# M_D_ext_power-with_d.net
KiCad netlist of a schematic drawn in EAGLE
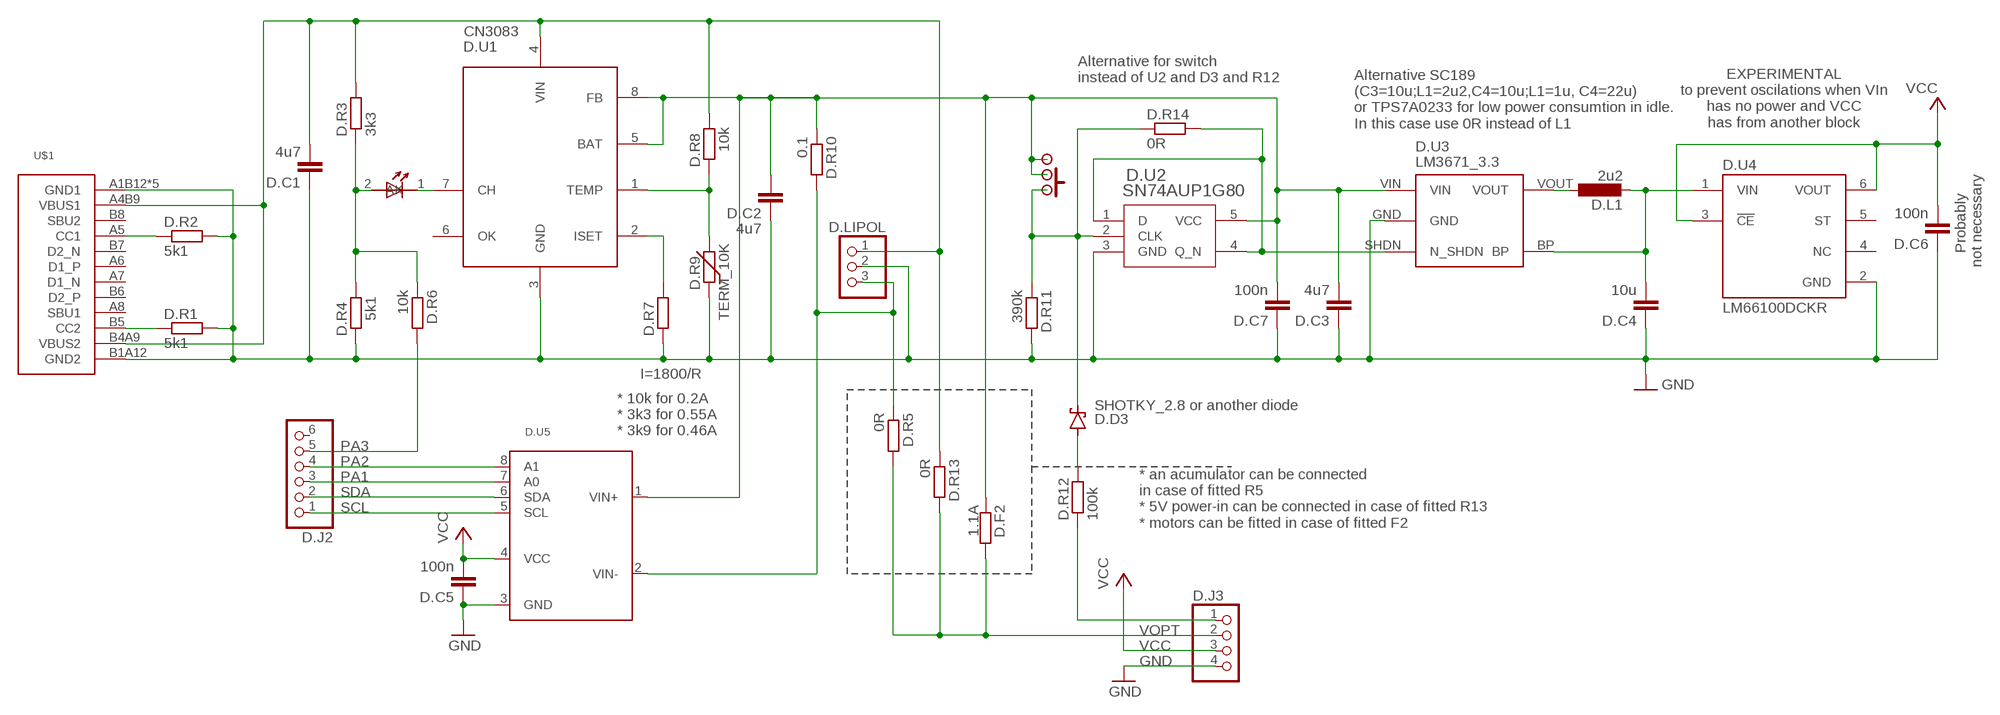
[diagram p0: schematic, sheet 1]

(export (version "E")
  (design (tool "Eeschema 10.0.6"))
  (components
    (comp (ref "D.C1")
      (value "4u7")
      (footprint "eagle-import:C0603")
      (libsource (lib "eagle-import") (part "C-EUC0603"))
    )
    (comp (ref "D.C2")
      (value "4u7")
      (footprint "eagle-import:C0603")
      (libsource (lib "eagle-import") (part "C-EUC0603"))
    )
    (comp (ref "D.C3")
      (value "4u7")
      (footprint "eagle-import:C0603")
      (libsource (lib "eagle-import") (part "C-EUC0603"))
    )
    (comp (ref "D.C4")
      (value "10u")
      (footprint "eagle-import:C0603")
      (libsource (lib "eagle-import") (part "C-EUC0603"))
    )
    (comp (ref "D.C5")
      (value "100n")
      (footprint "eagle-import:C0603")
      (libsource (lib "eagle-import") (part "C-EUC0603"))
    )
    (comp (ref "D.C6")
      (value "100n")
      (footprint "eagle-import:C0603")
      (libsource (lib "eagle-import") (part "C-EUC0603"))
    )
    (comp (ref "D.C7")
      (value "100n")
      (footprint "eagle-import:C0603")
      (libsource (lib "eagle-import") (part "C-EUC0603"))
    )
    (comp (ref "D.D1")
      (value "LED_1.8")
      (footprint "eagle-import:LED_1.8")
      (libsource (lib "eagle-import") (part "LED_1.8"))
    )
    (comp (ref "D.D3")
      (value "SHOTKY_2.8 or another diode")
      (footprint "eagle-import:SHOTKY_2.8")
      (libsource (lib "eagle-import") (part "SHOTKY_2.8"))
    )
    (comp (ref "D.F2")
      (value "1.1A")
      (footprint "eagle-import:R0805")
      (libsource (lib "eagle-import") (part "R-EU_R0805"))
    )
    (comp (ref "D.J2")
      (value "PINHD-1X6")
      (footprint "eagle-import:1X06")
      (libsource (lib "eagle-import") (part "PINHD-1X6"))
    )
    (comp (ref "D.J3")
      (value "PINHD-1X4")
      (footprint "eagle-import:1X04")
      (libsource (lib "eagle-import") (part "PINHD-1X4"))
    )
    (comp (ref "D.L1")
      (value "2u2")
      (footprint "eagle-import:L3230M")
      (libsource (lib "eagle-import") (part "L-EUL3230M"))
    )
    (comp (ref "D.LIPOL")
      (value "PINHEAD-1X3-2")
      (footprint "eagle-import:1X-03-2")
      (libsource (lib "eagle-import") (part "PINHEAD-1X3-2"))
    )
    (comp (ref "D.ON/OFF/RESET")
      (value "SWITCH")
      (footprint "eagle-import:SWITCH")
      (libsource (lib "eagle-import") (part "SWITCH"))
    )
    (comp (ref "D.R1")
      (value "5k1")
      (footprint "eagle-import:R0603")
      (libsource (lib "eagle-import") (part "R-EU_R0603"))
    )
    (comp (ref "D.R2")
      (value "5k1")
      (footprint "eagle-import:R0603")
      (libsource (lib "eagle-import") (part "R-EU_R0603"))
    )
    (comp (ref "D.R3")
      (value "3k3")
      (footprint "eagle-import:R0603")
      (libsource (lib "eagle-import") (part "R-EU_R0603"))
    )
    (comp (ref "D.R4")
      (value "5k1")
      (footprint "eagle-import:R0603")
      (libsource (lib "eagle-import") (part "R-EU_R0603"))
    )
    (comp (ref "D.R5")
      (value "0R")
      (footprint "eagle-import:R0603")
      (libsource (lib "eagle-import") (part "R-EU_R0603"))
    )
    (comp (ref "D.R6")
      (value "10k")
      (footprint "eagle-import:R0603")
      (libsource (lib "eagle-import") (part "R-EU_R0603"))
    )
    (comp (ref "D.R7")
      (value "I=1800/R")
      (footprint "eagle-import:R0603")
      (libsource (lib "eagle-import") (part "R-EU_R0603"))
    )
    (comp (ref "D.R8")
      (value "10k")
      (footprint "eagle-import:R0603")
      (libsource (lib "eagle-import") (part "R-EU_R0603"))
    )
    (comp (ref "D.R9")
      (value "TERM_10K")
      (footprint "eagle-import:THERM")
      (libsource (lib "eagle-import") (part "THERM"))
    )
    (comp (ref "D.R10")
      (value "0.1")
      (footprint "eagle-import:R0805")
      (libsource (lib "eagle-import") (part "R-EU_R0805"))
    )
    (comp (ref "D.R11")
      (value "390k")
      (footprint "eagle-import:R0603")
      (libsource (lib "eagle-import") (part "R-EU_R0603"))
    )
    (comp (ref "D.R12")
      (value "100k")
      (footprint "eagle-import:R0603")
      (libsource (lib "eagle-import") (part "R-EU_R0603"))
    )
    (comp (ref "D.R13")
      (value "0R")
      (footprint "eagle-import:R0603")
      (libsource (lib "eagle-import") (part "R-EU_R0603"))
    )
    (comp (ref "D.R14")
      (value "0R")
      (footprint "eagle-import:R0603")
      (libsource (lib "eagle-import") (part "R-EU_R0603"))
    )
    (comp (ref "D.U1")
      (value "CN3083")
      (footprint "eagle-import:SOP8")
      (libsource (lib "eagle-import") (part "CN3083"))
    )
    (comp (ref "D.U2")
      (value "SN74AUP1G80")
      (footprint "eagle-import:DCK0005A_M")
      (fields
        (field (name "MANUFACTURER_PART_NUMBER") "SN74AUP1G80DCKR")
        (field (name "COPYRIGHT") "Copyright (C) 2026 Ultra Librarian. All rights reserved.")
      )
      (libsource (lib "eagle-import") (part "SN74AUP1G80DCKRDCK0005A_M"))
    )
    (comp (ref "D.U3")
      (value "LM3671_3.3")
      (footprint "eagle-import:SOT32-5")
      (libsource (lib "eagle-import") (part "STABILISER_APE8865"))
    )
    (comp (ref "D.U4")
      (value "LM66100DCKR")
      (footprint "eagle-import:SOT65P210X110-6N")
      (fields (field (name "MF") "Texas Instruments"))
      (libsource (lib "eagle-import") (part "LM66100DCKR"))
    )
    (comp (ref "D.U5")
      (value "INA219")
      (footprint "eagle-import:SOT23-8")
      (libsource (lib "eagle-import") (part "INA219"))
    )
    (comp (ref "U$1")
      (value "USB-C")
      (footprint "eagle-import:USB-C")
      (libsource (lib "eagle-import") (part "USB-C"))
    )
  )
  (nets
    (net (code "1") (name "/PA1") (class "Default")
      (node (ref "D.J2") (pin "3") (pinfunction "3_3") (pintype "passive"))
      (node (ref "D.U5") (pin "7") (pinfunction "A0_7") (pintype "bidirectional"))
    )
    (net (code "2") (name "/PA2") (class "Default")
      (node (ref "D.J2") (pin "4") (pinfunction "4_4") (pintype "passive"))
      (node (ref "D.U5") (pin "8") (pinfunction "A1_8") (pintype "bidirectional"))
    )
    (net (code "3") (name "/PA3") (class "Default")
      (node (ref "D.J2") (pin "5") (pinfunction "5_5") (pintype "passive"))
      (node (ref "D.R6") (pin "2") (pinfunction "2_2") (pintype "passive"))
    )
    (net (code "4") (name "/SCL") (class "Default")
      (node (ref "D.J2") (pin "1") (pinfunction "1_1") (pintype "passive"))
      (node (ref "D.U5") (pin "5") (pinfunction "SCL_5") (pintype "bidirectional"))
    )
    (net (code "5") (name "/SDA") (class "Default")
      (node (ref "D.J2") (pin "2") (pinfunction "2_2") (pintype "passive"))
      (node (ref "D.U5") (pin "6") (pinfunction "SDA_6") (pintype "bidirectional"))
    )
    (net (code "6") (name "/VOPT") (class "Default")
      (node (ref "D.F2") (pin "2") (pinfunction "2_2") (pintype "passive"))
      (node (ref "D.J3") (pin "2") (pinfunction "2_2") (pintype "passive"))
      (node (ref "D.R13") (pin "2") (pinfunction "2_2") (pintype "passive"))
      (node (ref "D.R5") (pin "2") (pinfunction "2_2") (pintype "passive"))
    )
    (net (code "7") (name "GND") (class "Default")
      (node (ref "D.C1") (pin "1") (pinfunction "1_1") (pintype "passive"))
      (node (ref "D.C2") (pin "1") (pinfunction "1_1") (pintype "passive"))
      (node (ref "D.C3") (pin "1") (pinfunction "1_1") (pintype "passive"))
      (node (ref "D.C4") (pin "1") (pinfunction "1_1") (pintype "passive"))
      (node (ref "D.C5") (pin "1") (pinfunction "1_1") (pintype "passive"))
      (node (ref "D.C6") (pin "1") (pinfunction "1_1") (pintype "passive"))
      (node (ref "D.C7") (pin "1") (pinfunction "1_1") (pintype "passive"))
      (node (ref "D.J3") (pin "4") (pinfunction "4_4") (pintype "passive"))
      (node (ref "D.LIPOL") (pin "2") (pinfunction "2_2") (pintype "passive"))
      (node (ref "D.R1") (pin "2") (pinfunction "2_2") (pintype "passive"))
      (node (ref "D.R11") (pin "2") (pinfunction "2_2") (pintype "passive"))
      (node (ref "D.R2") (pin "2") (pinfunction "2_2") (pintype "passive"))
      (node (ref "D.R4") (pin "1") (pinfunction "1_1") (pintype "passive"))
      (node (ref "D.R7") (pin "1") (pinfunction "1_1") (pintype "passive"))
      (node (ref "D.R9") (pin "1") (pinfunction "1_1") (pintype "passive"))
      (node (ref "D.U1") (pin "3") (pinfunction "GND_3") (pintype "bidirectional"))
      (node (ref "D.U2") (pin "3") (pinfunction "GND_3") (pintype "power_in"))
      (node (ref "D.U3") (pin "GND") (pinfunction "GND_GND") (pintype "bidirectional"))
      (node (ref "D.U4") (pin "2") (pinfunction "GND_2") (pintype "power_in"))
      (node (ref "D.U5") (pin "3") (pinfunction "GND_3") (pintype "bidirectional"))
      (node (ref "U$1") (pin "A1B12") (pinfunction "GND1_A1B12") (pintype "bidirectional"))
      (node (ref "U$1") (pin "B1A12") (pinfunction "GND2_B1A12") (pintype "bidirectional"))
      (node (ref "U$1") (pin "SH1") (pinfunction "GND1_SH1") (pintype "bidirectional"))
      (node (ref "U$1") (pin "SH2") (pinfunction "GND1_SH2") (pintype "bidirectional"))
      (node (ref "U$1") (pin "SH3") (pinfunction "GND1_SH3") (pintype "bidirectional"))
      (node (ref "U$1") (pin "SH4") (pinfunction "GND1_SH4") (pintype "bidirectional"))
    )
    (net (code "8") (name "Net-(D.D1-A)") (class "Default")
      (node (ref "D.D1") (pin "2") (pinfunction "A_2") (pintype "bidirectional"))
      (node (ref "D.R3") (pin "1") (pinfunction "1_1") (pintype "passive"))
      (node (ref "D.R4") (pin "2") (pinfunction "2_2") (pintype "passive"))
      (node (ref "D.R6") (pin "1") (pinfunction "1_1") (pintype "passive"))
    )
    (net (code "9") (name "Net-(D.D1-K)") (class "Default")
      (node (ref "D.D1") (pin "1") (pinfunction "K_1") (pintype "bidirectional"))
      (node (ref "D.U1") (pin "7") (pinfunction "CH_7") (pintype "bidirectional"))
    )
    (net (code "10") (name "Net-(D.D3-C)") (class "Default")
      (node (ref "D.D3") (pin "K") (pinfunction "C_K") (pintype "passive"))
      (node (ref "D.ON/OFF/RESET") (pin "P$1") (pinfunction "P$1_P$1") (pintype "bidirectional"))
      (node (ref "D.ON/OFF/RESET") (pin "P$5") (pinfunction "P$1_P$5") (pintype "bidirectional"))
      (node (ref "D.ON/OFF/RESET") (pin "P$7") (pinfunction "P$1_P$7") (pintype "bidirectional"))
      (node (ref "D.R11") (pin "1") (pinfunction "1_1") (pintype "passive"))
      (node (ref "D.R14") (pin "1") (pinfunction "1_1") (pintype "passive"))
      (node (ref "D.U2") (pin "2") (pinfunction "CLK_2") (pintype "input"))
    )
    (net (code "11") (name "Net-(D.D3-PadA)") (class "Default")
      (node (ref "D.D3") (pin "A") (pinfunction "A_A") (pintype "passive"))
      (node (ref "D.R12") (pin "2") (pinfunction "2_2") (pintype "passive"))
    )
    (net (code "12") (name "Net-(D.J3-Pad1)") (class "Default")
      (node (ref "D.J3") (pin "1") (pinfunction "1_1") (pintype "passive"))
      (node (ref "D.R12") (pin "1") (pinfunction "1_1") (pintype "passive"))
    )
    (net (code "13") (name "Net-(D.L1-Pad1)") (class "Default")
      (node (ref "D.L1") (pin "1") (pinfunction "1_1") (pintype "passive"))
      (node (ref "D.U3") (pin "VOUT") (pinfunction "VOUT_VOUT") (pintype "bidirectional"))
    )
    (net (code "14") (name "Net-(D.U1-BAT)") (class "Default")
      (node (ref "D.C2") (pin "2") (pinfunction "2_2") (pintype "passive"))
      (node (ref "D.C3") (pin "2") (pinfunction "2_2") (pintype "passive"))
      (node (ref "D.C7") (pin "2") (pinfunction "2_2") (pintype "passive"))
      (node (ref "D.F2") (pin "1") (pinfunction "1_1") (pintype "passive"))
      (node (ref "D.ON/OFF/RESET") (pin "P$2") (pinfunction "P$2_P$2") (pintype "bidirectional"))
      (node (ref "D.ON/OFF/RESET") (pin "P$3") (pinfunction "P$3_P$3") (pintype "bidirectional"))
      (node (ref "D.ON/OFF/RESET") (pin "P$4") (pinfunction "P$3_P$4") (pintype "bidirectional"))
      (node (ref "D.ON/OFF/RESET") (pin "P$6") (pinfunction "P$3_P$6") (pintype "bidirectional"))
      (node (ref "D.R10") (pin "1") (pinfunction "1_1") (pintype "passive"))
      (node (ref "D.U1") (pin "5") (pinfunction "BAT_5") (pintype "bidirectional"))
      (node (ref "D.U1") (pin "8") (pinfunction "FB_8") (pintype "bidirectional"))
      (node (ref "D.U2") (pin "5") (pinfunction "VCC_5") (pintype "power_in"))
      (node (ref "D.U3") (pin "VIN") (pinfunction "VIN_VIN") (pintype "bidirectional"))
      (node (ref "D.U5") (pin "1") (pinfunction "VIN+_1") (pintype "bidirectional"))
    )
    (net (code "15") (name "Net-(D.U1-ISET)") (class "Default")
      (node (ref "D.R7") (pin "2") (pinfunction "2_2") (pintype "passive"))
      (node (ref "D.U1") (pin "2") (pinfunction "ISET_2") (pintype "bidirectional"))
    )
    (net (code "16") (name "Net-(D.U1-TEMP)") (class "Default")
      (node (ref "D.R8") (pin "1") (pinfunction "1_1") (pintype "passive"))
      (node (ref "D.R9") (pin "2") (pinfunction "2_2") (pintype "passive"))
      (node (ref "D.U1") (pin "1") (pinfunction "TEMP_1") (pintype "bidirectional"))
    )
    (net (code "17") (name "Net-(D.U1-VIN)") (class "Default")
      (node (ref "D.C1") (pin "2") (pinfunction "2_2") (pintype "passive"))
      (node (ref "D.LIPOL") (pin "1") (pinfunction "1_1") (pintype "passive"))
      (node (ref "D.R13") (pin "1") (pinfunction "1_1") (pintype "passive"))
      (node (ref "D.R3") (pin "2") (pinfunction "2_2") (pintype "passive"))
      (node (ref "D.R8") (pin "2") (pinfunction "2_2") (pintype "passive"))
      (node (ref "D.U1") (pin "4") (pinfunction "VIN_4") (pintype "bidirectional"))
      (node (ref "U$1") (pin "A4B9") (pinfunction "VBUS1_A4B9") (pintype "bidirectional"))
      (node (ref "U$1") (pin "B4A9") (pinfunction "VBUS2_B4A9") (pintype "bidirectional"))
    )
    (net (code "18") (name "Net-(D.U2-D)") (class "Default")
      (node (ref "D.R14") (pin "2") (pinfunction "2_2") (pintype "passive"))
      (node (ref "D.U2") (pin "1") (pinfunction "D_1") (pintype "input"))
      (node (ref "D.U2") (pin "4") (pinfunction "Q_N_4") (pintype "output"))
      (node (ref "D.U3") (pin "SHDN") (pinfunction "N_SHDN_SHDN") (pintype "bidirectional"))
    )
    (net (code "19") (name "Net-(D.U4-VIN)") (class "Default")
      (node (ref "D.C4") (pin "2") (pinfunction "2_2") (pintype "passive"))
      (node (ref "D.L1") (pin "2") (pinfunction "2_2") (pintype "passive"))
      (node (ref "D.U3") (pin "BP") (pinfunction "BP_BP") (pintype "bidirectional"))
      (node (ref "D.U4") (pin "1") (pinfunction "VIN_1") (pintype "input"))
    )
    (net (code "20") (name "Net-(D.U5-VIN-)") (class "Default")
      (node (ref "D.LIPOL") (pin "3") (pinfunction "3_3") (pintype "passive"))
      (node (ref "D.R10") (pin "2") (pinfunction "2_2") (pintype "passive"))
      (node (ref "D.R5") (pin "1") (pinfunction "1_1") (pintype "passive"))
      (node (ref "D.U5") (pin "2") (pinfunction "VIN-_2") (pintype "bidirectional"))
    )
    (net (code "21") (name "Net-(U$1-CC1)") (class "Default")
      (node (ref "D.R2") (pin "1") (pinfunction "1_1") (pintype "passive"))
      (node (ref "U$1") (pin "A5") (pinfunction "CC1_A5") (pintype "bidirectional"))
    )
    (net (code "22") (name "Net-(U$1-CC2)") (class "Default")
      (node (ref "D.R1") (pin "1") (pinfunction "1_1") (pintype "passive"))
      (node (ref "U$1") (pin "B5") (pinfunction "CC2_B5") (pintype "bidirectional"))
    )
    (net (code "23") (name "VCC") (class "Default")
      (node (ref "D.C5") (pin "2") (pinfunction "2_2") (pintype "passive"))
      (node (ref "D.C6") (pin "2") (pinfunction "2_2") (pintype "passive"))
      (node (ref "D.J3") (pin "3") (pinfunction "3_3") (pintype "passive"))
      (node (ref "D.U4") (pin "3") (pinfunction "~{CE}_3") (pintype "input"))
      (node (ref "D.U4") (pin "6") (pinfunction "VOUT_6") (pintype "output"))
      (node (ref "D.U5") (pin "4") (pinfunction "VCC_4") (pintype "bidirectional"))
    )
    (net (code "24") (name "unconnected-(D.J2-Pad6)") (class "Default")
      (node (ref "D.J2") (pin "6") (pinfunction "6_6") (pintype "passive"))
    )
    (net (code "25") (name "unconnected-(D.U1-OK-Pad6)") (class "Default")
      (node (ref "D.U1") (pin "6") (pinfunction "OK_6") (pintype "bidirectional"))
    )
    (net (code "26") (name "unconnected-(D.U4-NC-Pad4)") (class "Default")
      (node (ref "D.U4") (pin "4") (pinfunction "NC_4") (pintype "no_connect"))
    )
    (net (code "27") (name "unconnected-(D.U4-ST-Pad5)") (class "Default")
      (node (ref "D.U4") (pin "5") (pinfunction "ST_5") (pintype "output"))
    )
    (net (code "28") (name "unconnected-(U$1-D1_N-PadA7)") (class "Default")
      (node (ref "U$1") (pin "A7") (pinfunction "D1_N_A7") (pintype "bidirectional"))
    )
    (net (code "29") (name "unconnected-(U$1-D1_P-PadA6)") (class "Default")
      (node (ref "U$1") (pin "A6") (pinfunction "D1_P_A6") (pintype "bidirectional"))
    )
    (net (code "30") (name "unconnected-(U$1-D2_N-PadB7)") (class "Default")
      (node (ref "U$1") (pin "B7") (pinfunction "D2_N_B7") (pintype "bidirectional"))
    )
    (net (code "31") (name "unconnected-(U$1-D2_P-PadB6)") (class "Default")
      (node (ref "U$1") (pin "B6") (pinfunction "D2_P_B6") (pintype "bidirectional"))
    )
    (net (code "32") (name "unconnected-(U$1-SBU1-PadA8)") (class "Default")
      (node (ref "U$1") (pin "A8") (pinfunction "SBU1_A8") (pintype "bidirectional"))
    )
    (net (code "33") (name "unconnected-(U$1-SBU2-PadB8)") (class "Default")
      (node (ref "U$1") (pin "B8") (pinfunction "SBU2_B8") (pintype "bidirectional"))
    )
  )
)
